# Inverter.net
KiCad netlist of a schematic drawn in EAGLE
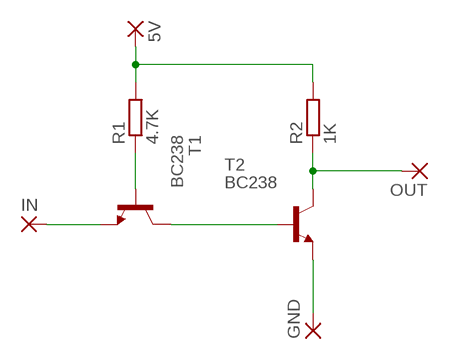
[diagram p0: schematic, sheet 1]

(export (version "E")
  (design (tool "Eeschema 10.0.6"))
  (components
    (comp (ref "5V")
      (value "2,54/0,8")
      (footprint "eagle-import:2,54_0,8")
      (libsource (lib "eagle-import") (part "2,54/0,8"))
    )
    (comp (ref "GND")
      (value "2,54/0,8")
      (footprint "eagle-import:2,54_0,8")
      (libsource (lib "eagle-import") (part "2,54/0,8"))
    )
    (comp (ref "IN")
      (value "2,54/0,8")
      (footprint "eagle-import:2,54_0,8")
      (libsource (lib "eagle-import") (part "2,54/0,8"))
    )
    (comp (ref "OUT")
      (value "2,54/0,8")
      (footprint "eagle-import:2,54_0,8")
      (libsource (lib "eagle-import") (part "2,54/0,8"))
    )
    (comp (ref "R1")
      (value "4.7K")
      (footprint "eagle-import:0204_7")
      (libsource (lib "eagle-import") (part "R-EU_0204/7"))
    )
    (comp (ref "R2")
      (value "1K")
      (footprint "eagle-import:0204_7")
      (libsource (lib "eagle-import") (part "R-EU_0204/7"))
    )
    (comp (ref "T1")
      (value "BC238")
      (footprint "eagle-import:TO92")
      (libsource (lib "eagle-import") (part "BC238"))
    )
    (comp (ref "T2")
      (value "BC238")
      (footprint "eagle-import:TO92")
      (libsource (lib "eagle-import") (part "BC238"))
    )
  )
  (nets
    (net (code "1") (name "Net-(5V-P)") (class "Default")
      (node (ref "5V") (pin "1") (pinfunction "P_1") (pintype "passive"))
      (node (ref "R1") (pin "2") (pinfunction "2_2") (pintype "passive"))
      (node (ref "R2") (pin "2") (pinfunction "2_2") (pintype "passive"))
    )
    (net (code "2") (name "Net-(GND-P)") (class "Default")
      (node (ref "GND") (pin "1") (pinfunction "P_1") (pintype "passive"))
      (node (ref "T2") (pin "1") (pinfunction "E_1") (pintype "passive"))
    )
    (net (code "3") (name "Net-(IN-P)") (class "Default")
      (node (ref "IN") (pin "1") (pinfunction "P_1") (pintype "passive"))
      (node (ref "T1") (pin "1") (pinfunction "E_1") (pintype "passive"))
    )
    (net (code "4") (name "Net-(OUT-P)") (class "Default")
      (node (ref "OUT") (pin "1") (pinfunction "P_1") (pintype "passive"))
      (node (ref "R2") (pin "1") (pinfunction "1_1") (pintype "passive"))
      (node (ref "T2") (pin "3") (pinfunction "C_3") (pintype "passive"))
    )
    (net (code "5") (name "Net-(T1-B)") (class "Default")
      (node (ref "R1") (pin "1") (pinfunction "1_1") (pintype "passive"))
      (node (ref "T1") (pin "2") (pinfunction "B_2") (pintype "passive"))
    )
    (net (code "6") (name "Net-(T1-C)") (class "Default")
      (node (ref "T1") (pin "3") (pinfunction "C_3") (pintype "passive"))
      (node (ref "T2") (pin "2") (pinfunction "B_2") (pintype "passive"))
    )
  )
)
